# ProgrammableOLED.net
KiCad netlist of a schematic drawn in EAGLE
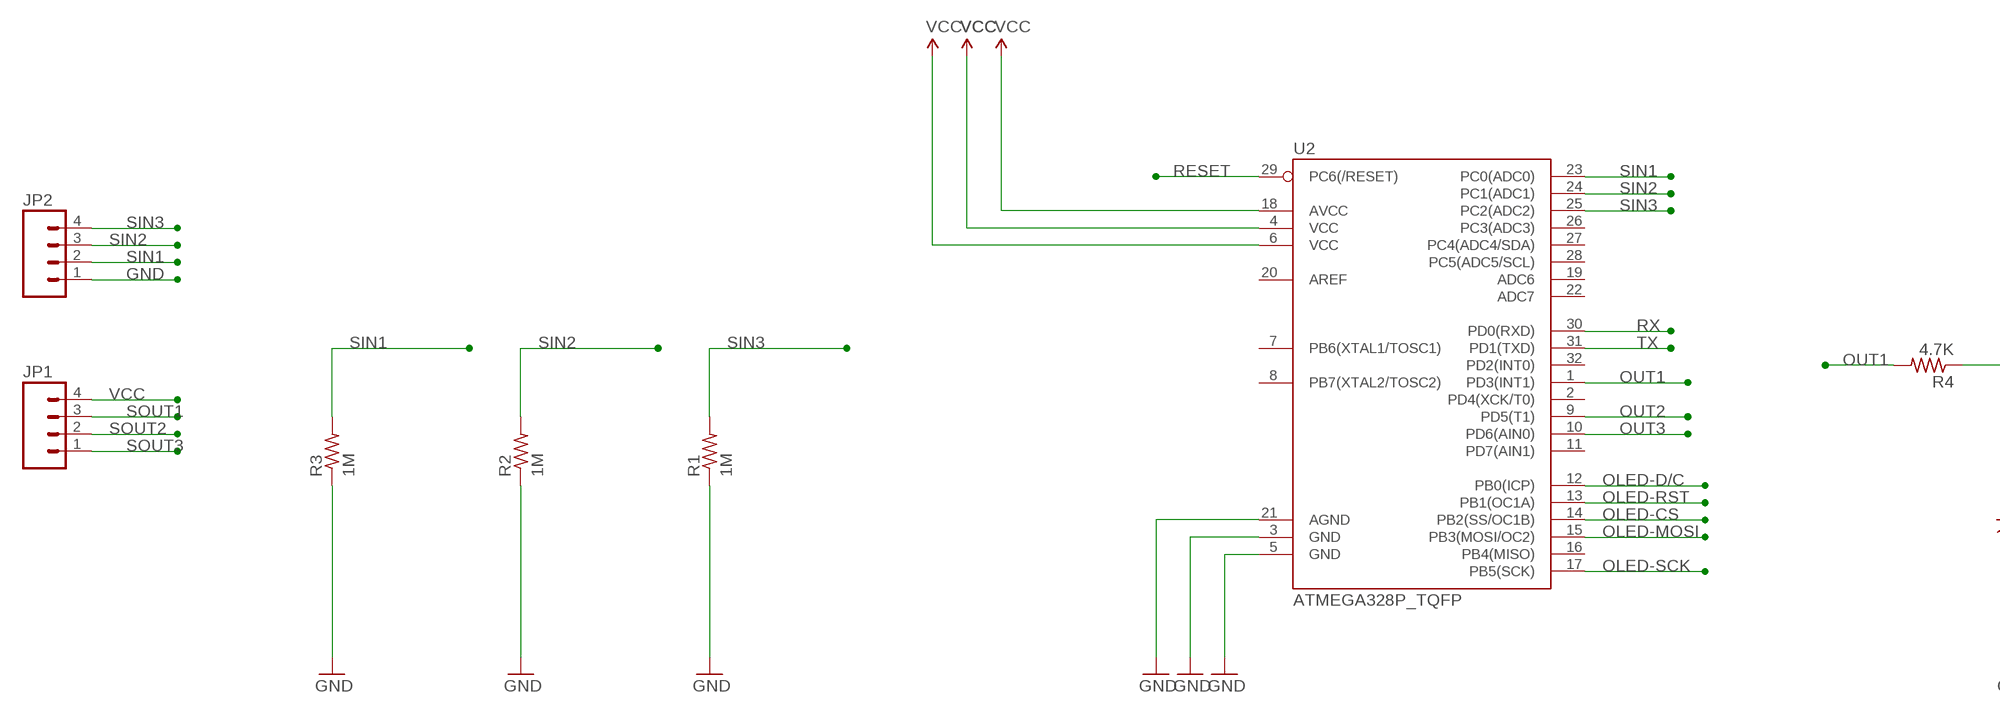
[diagram p0: schematic, sheet 1, part 1 of 2]
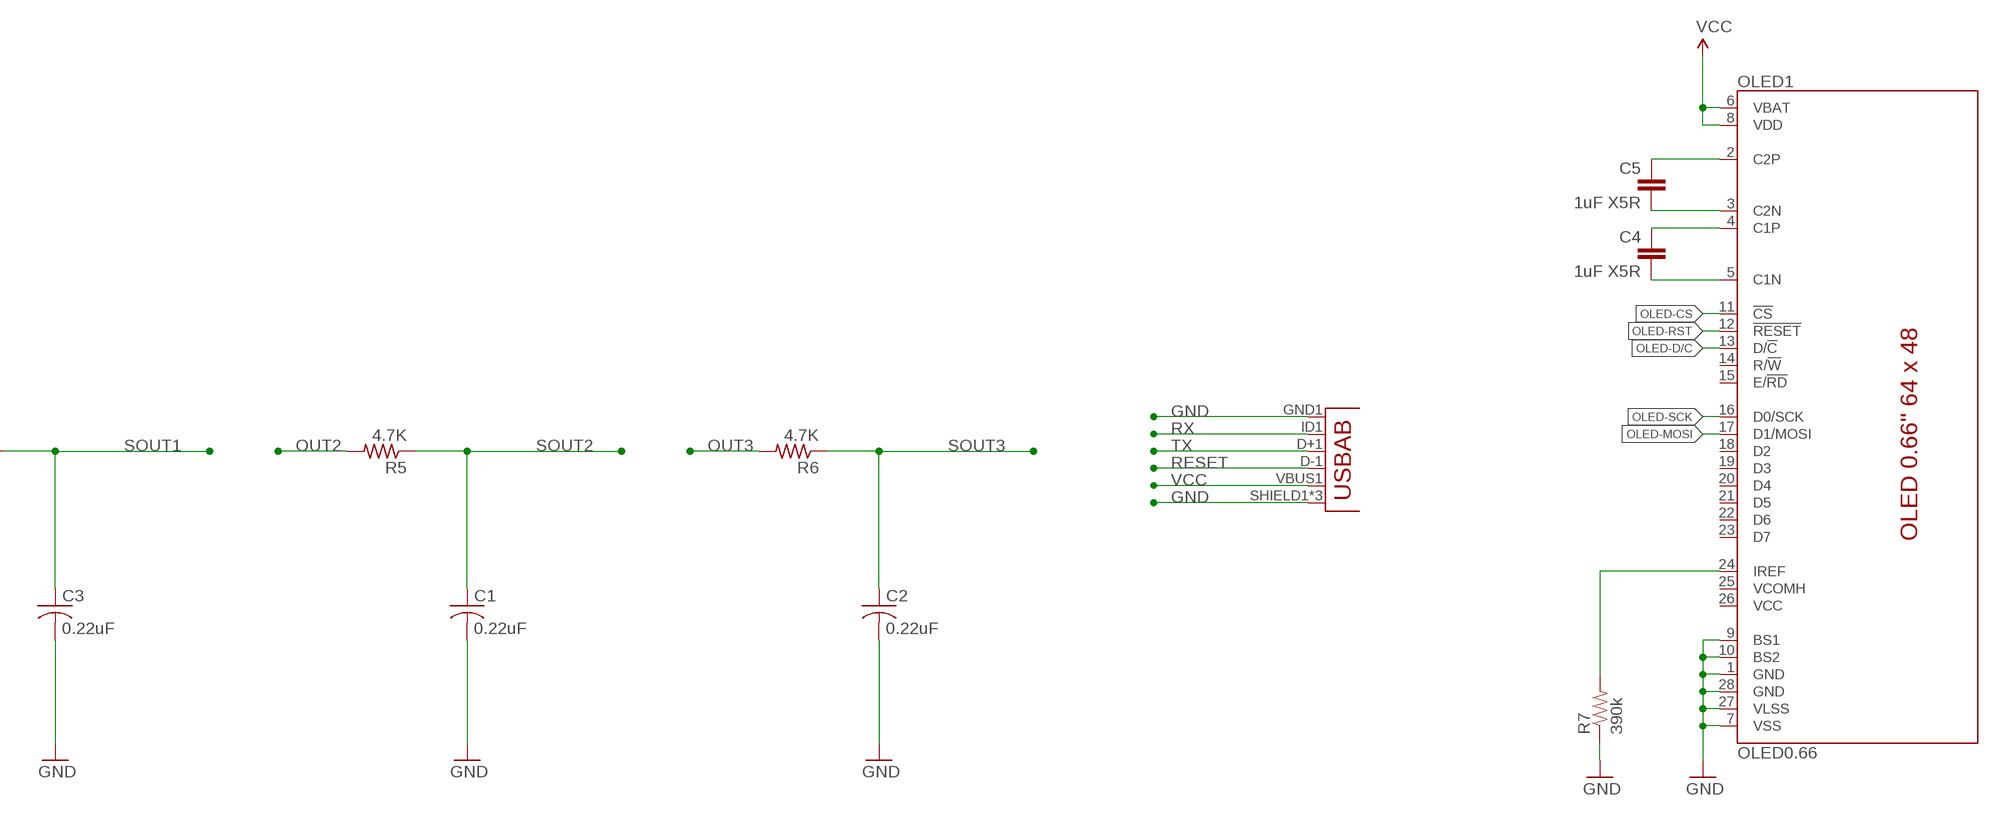
[diagram p1: schematic, sheet 1, part 2 of 2]

(export (version "E")
  (design (tool "Eeschema 10.0.6"))
  (components
    (comp (ref "C1")
      (value "0.22uF")
      (footprint "eagle-import:C0603")
      (libsource (lib "eagle-import") (part "C-USC0603"))
    )
    (comp (ref "C2")
      (value "0.22uF")
      (footprint "eagle-import:C0603")
      (libsource (lib "eagle-import") (part "C-USC0603"))
    )
    (comp (ref "C3")
      (value "0.22uF")
      (footprint "eagle-import:C0603")
      (libsource (lib "eagle-import") (part "C-USC0603"))
    )
    (comp (ref "C4")
      (value "1uF X5R")
      (footprint "eagle-import:0805")
      (libsource (lib "eagle-import") (part "CAP0805"))
    )
    (comp (ref "C5")
      (value "1uF X5R")
      (footprint "eagle-import:0805")
      (libsource (lib "eagle-import") (part "CAP0805"))
    )
    (comp (ref "JP1")
      (value "M04PTH")
      (footprint "eagle-import:1X04")
      (libsource (lib "eagle-import") (part "M04PTH"))
    )
    (comp (ref "JP2")
      (value "M04PTH")
      (footprint "eagle-import:1X04")
      (libsource (lib "eagle-import") (part "M04PTH"))
    )
    (comp (ref "JP5")
      (value "USB-ABCONN-11794")
      (footprint "eagle-import:USB-AB-MICRO-SMD_V03")
      (libsource (lib "eagle-import") (part "USB-ABCONN-11794"))
    )
    (comp (ref "OLED1")
      (value "OLED0.66")
      (footprint "eagle-import:OLED-0.66-64X48")
      (libsource (lib "eagle-import") (part "OLED0.66"))
    )
    (comp (ref "R1")
      (value "1M")
      (footprint "eagle-import:R0603")
      (libsource (lib "eagle-import") (part "R-US_R0603"))
    )
    (comp (ref "R2")
      (value "1M")
      (footprint "eagle-import:R0603")
      (libsource (lib "eagle-import") (part "R-US_R0603"))
    )
    (comp (ref "R3")
      (value "1M")
      (footprint "eagle-import:R0603")
      (libsource (lib "eagle-import") (part "R-US_R0603"))
    )
    (comp (ref "R4")
      (value "4.7K")
      (footprint "eagle-import:R0603")
      (libsource (lib "eagle-import") (part "R-US_R0603"))
    )
    (comp (ref "R5")
      (value "4.7K")
      (footprint "eagle-import:R0603")
      (libsource (lib "eagle-import") (part "R-US_R0603"))
    )
    (comp (ref "R6")
      (value "4.7K")
      (footprint "eagle-import:R0603")
      (libsource (lib "eagle-import") (part "R-US_R0603"))
    )
    (comp (ref "R7")
      (value "390k")
      (footprint "eagle-import:0603-RES")
      (libsource (lib "eagle-import") (part "RESISTOR0603-RES"))
    )
    (comp (ref "U2")
      (value "ATMEGA328P_TQFP")
      (footprint "eagle-import:TQFP32-08")
      (libsource (lib "eagle-import") (part "ATMEGA328P_TQFP"))
    )
  )
  (nets
    (net (code "1") (name "/OUT1") (class "Default")
      (node (ref "R4") (pin "2") (pinfunction "2_2") (pintype "passive"))
      (node (ref "U2") (pin "1") (pinfunction "PD3(INT1)_1") (pintype "bidirectional"))
    )
    (net (code "2") (name "/OUT2") (class "Default")
      (node (ref "R5") (pin "2") (pinfunction "2_2") (pintype "passive"))
      (node (ref "U2") (pin "9") (pinfunction "PD5(T1)_9") (pintype "bidirectional"))
    )
    (net (code "3") (name "/OUT3") (class "Default")
      (node (ref "R6") (pin "2") (pinfunction "2_2") (pintype "passive"))
      (node (ref "U2") (pin "10") (pinfunction "PD6(AIN0)_10") (pintype "bidirectional"))
    )
    (net (code "4") (name "/RESET") (class "Default")
      (node (ref "JP5") (pin "D-1") (pinfunction "D-_D-1") (pintype "bidirectional"))
      (node (ref "U2") (pin "29") (pinfunction "PC6(/RESET)_29") (pintype "bidirectional"))
    )
    (net (code "5") (name "/RX") (class "Default")
      (node (ref "JP5") (pin "ID1") (pinfunction "USBID_ID1") (pintype "bidirectional"))
      (node (ref "U2") (pin "30") (pinfunction "PD0(RXD)_30") (pintype "bidirectional"))
    )
    (net (code "6") (name "/SIN1") (class "Default")
      (node (ref "JP2") (pin "2") (pinfunction "2_2") (pintype "passive"))
      (node (ref "R3") (pin "2") (pinfunction "2_2") (pintype "passive"))
      (node (ref "U2") (pin "23") (pinfunction "PC0(ADC0)_23") (pintype "bidirectional"))
    )
    (net (code "7") (name "/SIN2") (class "Default")
      (node (ref "JP2") (pin "3") (pinfunction "3_3") (pintype "passive"))
      (node (ref "R2") (pin "2") (pinfunction "2_2") (pintype "passive"))
      (node (ref "U2") (pin "24") (pinfunction "PC1(ADC1)_24") (pintype "bidirectional"))
    )
    (net (code "8") (name "/SIN3") (class "Default")
      (node (ref "JP2") (pin "4") (pinfunction "4_4") (pintype "passive"))
      (node (ref "R1") (pin "2") (pinfunction "2_2") (pintype "passive"))
      (node (ref "U2") (pin "25") (pinfunction "PC2(ADC2)_25") (pintype "bidirectional"))
    )
    (net (code "9") (name "/SOUT1") (class "Default")
      (node (ref "C3") (pin "1") (pinfunction "1_1") (pintype "passive"))
      (node (ref "JP1") (pin "3") (pinfunction "3_3") (pintype "passive"))
      (node (ref "R4") (pin "1") (pinfunction "1_1") (pintype "passive"))
    )
    (net (code "10") (name "/SOUT2") (class "Default")
      (node (ref "C1") (pin "1") (pinfunction "1_1") (pintype "passive"))
      (node (ref "JP1") (pin "2") (pinfunction "2_2") (pintype "passive"))
      (node (ref "R5") (pin "1") (pinfunction "1_1") (pintype "passive"))
    )
    (net (code "11") (name "/SOUT3") (class "Default")
      (node (ref "C2") (pin "1") (pinfunction "1_1") (pintype "passive"))
      (node (ref "JP1") (pin "1") (pinfunction "1_1") (pintype "passive"))
      (node (ref "R6") (pin "1") (pinfunction "1_1") (pintype "passive"))
    )
    (net (code "12") (name "/TX") (class "Default")
      (node (ref "JP5") (pin "D+1") (pinfunction "D+_D+1") (pintype "bidirectional"))
      (node (ref "U2") (pin "31") (pinfunction "PD1(TXD)_31") (pintype "bidirectional"))
    )
    (net (code "13") (name "GND") (class "Default")
      (node (ref "C1") (pin "2") (pinfunction "2_2") (pintype "passive"))
      (node (ref "C2") (pin "2") (pinfunction "2_2") (pintype "passive"))
      (node (ref "C3") (pin "2") (pinfunction "2_2") (pintype "passive"))
      (node (ref "JP2") (pin "1") (pinfunction "1_1") (pintype "passive"))
      (node (ref "JP5") (pin "GND1") (pinfunction "GND_GND1") (pintype "bidirectional"))
      (node (ref "JP5") (pin "SHIELD1") (pinfunction "SHIELD_SHIELD1") (pintype "bidirectional"))
      (node (ref "JP5") (pin "SHIELD2") (pinfunction "SHIELD_SHIELD2") (pintype "bidirectional"))
      (node (ref "JP5") (pin "SHIELD3") (pinfunction "SHIELD_SHIELD3") (pintype "bidirectional"))
      (node (ref "OLED1") (pin "1") (pinfunction "GND_1") (pintype "bidirectional"))
      (node (ref "OLED1") (pin "10") (pinfunction "BS2_10") (pintype "bidirectional"))
      (node (ref "OLED1") (pin "27") (pinfunction "VLSS_27") (pintype "bidirectional"))
      (node (ref "OLED1") (pin "28") (pinfunction "GND_28") (pintype "bidirectional"))
      (node (ref "OLED1") (pin "7") (pinfunction "VSS_7") (pintype "bidirectional"))
      (node (ref "OLED1") (pin "9") (pinfunction "BS1_9") (pintype "bidirectional"))
      (node (ref "R1") (pin "1") (pinfunction "1_1") (pintype "passive"))
      (node (ref "R2") (pin "1") (pinfunction "1_1") (pintype "passive"))
      (node (ref "R3") (pin "1") (pinfunction "1_1") (pintype "passive"))
      (node (ref "R7") (pin "1") (pinfunction "1_1") (pintype "passive"))
      (node (ref "U2") (pin "21") (pinfunction "AGND_21") (pintype "bidirectional"))
      (node (ref "U2") (pin "3") (pinfunction "GND_3") (pintype "bidirectional"))
      (node (ref "U2") (pin "5") (pinfunction "GND_5") (pintype "bidirectional"))
    )
    (net (code "14") (name "Net-(OLED1-C1N)") (class "Default")
      (node (ref "C4") (pin "2") (pinfunction "2_2") (pintype "passive"))
      (node (ref "OLED1") (pin "5") (pinfunction "C1N_5") (pintype "bidirectional"))
    )
    (net (code "15") (name "Net-(OLED1-C1P)") (class "Default")
      (node (ref "C4") (pin "1") (pinfunction "1_1") (pintype "passive"))
      (node (ref "OLED1") (pin "4") (pinfunction "C1P_4") (pintype "bidirectional"))
    )
    (net (code "16") (name "Net-(OLED1-C2N)") (class "Default")
      (node (ref "C5") (pin "2") (pinfunction "2_2") (pintype "passive"))
      (node (ref "OLED1") (pin "3") (pinfunction "C2N_3") (pintype "bidirectional"))
    )
    (net (code "17") (name "Net-(OLED1-C2P)") (class "Default")
      (node (ref "C5") (pin "1") (pinfunction "1_1") (pintype "passive"))
      (node (ref "OLED1") (pin "2") (pinfunction "C2P_2") (pintype "bidirectional"))
    )
    (net (code "18") (name "Net-(OLED1-IREF)") (class "Default")
      (node (ref "OLED1") (pin "24") (pinfunction "IREF_24") (pintype "bidirectional"))
      (node (ref "R7") (pin "2") (pinfunction "2_2") (pintype "passive"))
    )
    (net (code "19") (name "OLED-CS") (class "Default")
      (node (ref "OLED1") (pin "11") (pinfunction "~{CS}_11") (pintype "bidirectional"))
      (node (ref "U2") (pin "14") (pinfunction "PB2(SS/OC1B)_14") (pintype "bidirectional"))
    )
    (net (code "20") (name "OLED-D{slash}C") (class "Default")
      (node (ref "OLED1") (pin "13") (pinfunction "D/~{C}_13") (pintype "bidirectional"))
      (node (ref "U2") (pin "12") (pinfunction "PB0(ICP)_12") (pintype "bidirectional"))
    )
    (net (code "21") (name "OLED-MOSI") (class "Default")
      (node (ref "OLED1") (pin "17") (pinfunction "D1/MOSI_17") (pintype "bidirectional"))
      (node (ref "U2") (pin "15") (pinfunction "PB3(MOSI/OC2)_15") (pintype "bidirectional"))
    )
    (net (code "22") (name "OLED-RST") (class "Default")
      (node (ref "OLED1") (pin "12") (pinfunction "~{RESET}_12") (pintype "bidirectional"))
      (node (ref "U2") (pin "13") (pinfunction "PB1(OC1A)_13") (pintype "bidirectional"))
    )
    (net (code "23") (name "OLED-SCK") (class "Default")
      (node (ref "OLED1") (pin "16") (pinfunction "D0/SCK_16") (pintype "bidirectional"))
      (node (ref "U2") (pin "17") (pinfunction "PB5(SCK)_17") (pintype "bidirectional"))
    )
    (net (code "24") (name "VCC") (class "Default")
      (node (ref "JP1") (pin "4") (pinfunction "4_4") (pintype "passive"))
      (node (ref "JP5") (pin "VBUS1") (pinfunction "VBUS_VBUS1") (pintype "bidirectional"))
      (node (ref "OLED1") (pin "6") (pinfunction "VBAT_6") (pintype "bidirectional"))
      (node (ref "OLED1") (pin "8") (pinfunction "VDD_8") (pintype "bidirectional"))
      (node (ref "U2") (pin "18") (pinfunction "AVCC_18") (pintype "bidirectional"))
      (node (ref "U2") (pin "4") (pinfunction "VCC_4") (pintype "bidirectional"))
      (node (ref "U2") (pin "6") (pinfunction "VCC_6") (pintype "bidirectional"))
    )
    (net (code "25") (name "unconnected-(OLED1-D2-Pad18)") (class "Default")
      (node (ref "OLED1") (pin "18") (pinfunction "D2_18") (pintype "bidirectional"))
    )
    (net (code "26") (name "unconnected-(OLED1-D3-Pad19)") (class "Default")
      (node (ref "OLED1") (pin "19") (pinfunction "D3_19") (pintype "bidirectional"))
    )
    (net (code "27") (name "unconnected-(OLED1-D4-Pad20)") (class "Default")
      (node (ref "OLED1") (pin "20") (pinfunction "D4_20") (pintype "bidirectional"))
    )
    (net (code "28") (name "unconnected-(OLED1-D5-Pad21)") (class "Default")
      (node (ref "OLED1") (pin "21") (pinfunction "D5_21") (pintype "bidirectional"))
    )
    (net (code "29") (name "unconnected-(OLED1-D6-Pad22)") (class "Default")
      (node (ref "OLED1") (pin "22") (pinfunction "D6_22") (pintype "bidirectional"))
    )
    (net (code "30") (name "unconnected-(OLED1-D7-Pad23)") (class "Default")
      (node (ref "OLED1") (pin "23") (pinfunction "D7_23") (pintype "bidirectional"))
    )
    (net (code "31") (name "unconnected-(OLED1-E{slash}~{RD}-Pad15)") (class "Default")
      (node (ref "OLED1") (pin "15") (pinfunction "E/~{RD}_15") (pintype "bidirectional"))
    )
    (net (code "32") (name "unconnected-(OLED1-R{slash}~{W}-Pad14)") (class "Default")
      (node (ref "OLED1") (pin "14") (pinfunction "R/~{W}_14") (pintype "bidirectional"))
    )
    (net (code "33") (name "unconnected-(OLED1-VCC-Pad26)") (class "Default")
      (node (ref "OLED1") (pin "26") (pinfunction "VCC_26") (pintype "bidirectional"))
    )
    (net (code "34") (name "unconnected-(OLED1-VCOMH-Pad25)") (class "Default")
      (node (ref "OLED1") (pin "25") (pinfunction "VCOMH_25") (pintype "bidirectional"))
    )
    (net (code "35") (name "unconnected-(U2-ADC6-Pad19)") (class "Default")
      (node (ref "U2") (pin "19") (pinfunction "ADC6_19") (pintype "bidirectional"))
    )
    (net (code "36") (name "unconnected-(U2-ADC7-Pad22)") (class "Default")
      (node (ref "U2") (pin "22") (pinfunction "ADC7_22") (pintype "bidirectional"))
    )
    (net (code "37") (name "unconnected-(U2-AREF-Pad20)") (class "Default")
      (node (ref "U2") (pin "20") (pinfunction "AREF_20") (pintype "bidirectional"))
    )
    (net (code "38") (name "unconnected-(U2-PB4(MISO)-Pad16)") (class "Default")
      (node (ref "U2") (pin "16") (pinfunction "PB4(MISO)_16") (pintype "bidirectional"))
    )
    (net (code "39") (name "unconnected-(U2-PB6(XTAL1{slash}TOSC1)-Pad7)") (class "Default")
      (node (ref "U2") (pin "7") (pinfunction "PB6(XTAL1/TOSC1)_7") (pintype "bidirectional"))
    )
    (net (code "40") (name "unconnected-(U2-PB7(XTAL2{slash}TOSC2)-Pad8)") (class "Default")
      (node (ref "U2") (pin "8") (pinfunction "PB7(XTAL2/TOSC2)_8") (pintype "bidirectional"))
    )
    (net (code "41") (name "unconnected-(U2-PC3(ADC3)-Pad26)") (class "Default")
      (node (ref "U2") (pin "26") (pinfunction "PC3(ADC3)_26") (pintype "bidirectional"))
    )
    (net (code "42") (name "unconnected-(U2-PC4(ADC4{slash}SDA)-Pad27)") (class "Default")
      (node (ref "U2") (pin "27") (pinfunction "PC4(ADC4/SDA)_27") (pintype "bidirectional"))
    )
    (net (code "43") (name "unconnected-(U2-PC5(ADC5{slash}SCL)-Pad28)") (class "Default")
      (node (ref "U2") (pin "28") (pinfunction "PC5(ADC5/SCL)_28") (pintype "bidirectional"))
    )
    (net (code "44") (name "unconnected-(U2-PD2(INT0)-Pad32)") (class "Default")
      (node (ref "U2") (pin "32") (pinfunction "PD2(INT0)_32") (pintype "bidirectional"))
    )
    (net (code "45") (name "unconnected-(U2-PD4(XCK{slash}T0)-Pad2)") (class "Default")
      (node (ref "U2") (pin "2") (pinfunction "PD4(XCK/T0)_2") (pintype "bidirectional"))
    )
    (net (code "46") (name "unconnected-(U2-PD7(AIN1)-Pad11)") (class "Default")
      (node (ref "U2") (pin "11") (pinfunction "PD7(AIN1)_11") (pintype "bidirectional"))
    )
  )
)
